# tomu-eagle0.net
KiCad netlist of a schematic drawn in EAGLE
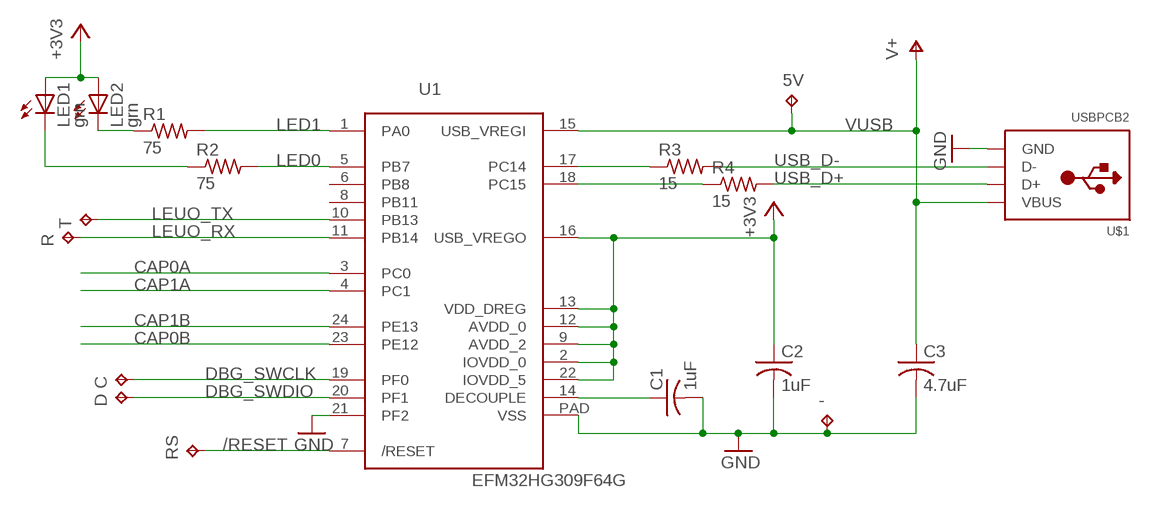
[diagram p0: schematic, sheet 1]

(export (version "E")
  (design (tool "Eeschema 10.0.6"))
  (components
    (comp (ref "-")
      (value "TPTP10SQ")
      (footprint "eagle-import:TP10SQ")
      (libsource (lib "eagle-import") (part "TPTP10SQ"))
    )
    (comp (ref "5V")
      (value "TPTP10R")
      (footprint "eagle-import:TP10R")
      (libsource (lib "eagle-import") (part "TPTP10R"))
    )
    (comp (ref "C")
      (value "TPTP10R")
      (footprint "eagle-import:TP10R")
      (libsource (lib "eagle-import") (part "TPTP10R"))
    )
    (comp (ref "C1")
      (value "1uF")
      (footprint "eagle-import:C0402K")
      (libsource (lib "eagle-import") (part "C-USC0402K"))
    )
    (comp (ref "C2")
      (value "1uF")
      (footprint "eagle-import:C0402K")
      (libsource (lib "eagle-import") (part "C-USC0402K"))
    )
    (comp (ref "C3")
      (value "4.7uF")
      (footprint "eagle-import:C0402K")
      (libsource (lib "eagle-import") (part "C-USC0402K"))
    )
    (comp (ref "D")
      (value "TPTP10R")
      (footprint "eagle-import:TP10R")
      (libsource (lib "eagle-import") (part "TPTP10R"))
    )
    (comp (ref "LED1")
      (value "grn")
      (footprint "eagle-import:CHIP-LED0603")
      (libsource (lib "eagle-import") (part "LEDCHIP-LED0603"))
    )
    (comp (ref "LED2")
      (value "grn")
      (footprint "eagle-import:CHIP-LED0603")
      (libsource (lib "eagle-import") (part "LEDCHIP-LED0603"))
    )
    (comp (ref "R")
      (value "TPTP10R")
      (footprint "eagle-import:TP10R")
      (libsource (lib "eagle-import") (part "TPTP10R"))
    )
    (comp (ref "R1")
      (value "75")
      (footprint "eagle-import:R0402")
      (libsource (lib "eagle-import") (part "R-US_R0402"))
    )
    (comp (ref "R2")
      (value "75")
      (footprint "eagle-import:R0402")
      (libsource (lib "eagle-import") (part "R-US_R0402"))
    )
    (comp (ref "R3")
      (value "15")
      (footprint "eagle-import:R0402")
      (libsource (lib "eagle-import") (part "R-US_R0402"))
    )
    (comp (ref "R4")
      (value "15")
      (footprint "eagle-import:R0402")
      (libsource (lib "eagle-import") (part "R-US_R0402"))
    )
    (comp (ref "RS")
      (value "TPTP10R")
      (footprint "eagle-import:TP10R")
      (libsource (lib "eagle-import") (part "TPTP10R"))
    )
    (comp (ref "T")
      (value "TPTP10R")
      (footprint "eagle-import:TP10R")
      (libsource (lib "eagle-import") (part "TPTP10R"))
    )
    (comp (ref "U$1")
      (value "USBPCB2")
      (footprint "eagle-import:USB-A-PCB-2")
      (libsource (lib "eagle-import") (part "USBPCB2"))
    )
    (comp (ref "U1")
      (value "EFM32HG309F64G")
      (footprint "eagle-import:QFN24PAD")
      (libsource (lib "eagle-import") (part "EFM32HG309F64G"))
    )
  )
  (nets
    (net (code "1") (name "+3V3") (class "Default")
      (node (ref "C2") (pin "1") (pinfunction "1_1") (pintype "passive"))
      (node (ref "LED1") (pin "A") (pinfunction "A_A") (pintype "passive"))
      (node (ref "LED2") (pin "A") (pinfunction "A_A") (pintype "passive"))
      (node (ref "U1") (pin "12") (pinfunction "AVDD_0_12") (pintype "bidirectional"))
      (node (ref "U1") (pin "13") (pinfunction "VDD_DREG_13") (pintype "bidirectional"))
      (node (ref "U1") (pin "16") (pinfunction "USB_VREGO_16") (pintype "bidirectional"))
      (node (ref "U1") (pin "2") (pinfunction "IOVDD_0_2") (pintype "bidirectional"))
      (node (ref "U1") (pin "22") (pinfunction "IOVDD_5_22") (pintype "bidirectional"))
      (node (ref "U1") (pin "9") (pinfunction "AVDD_2_9") (pintype "bidirectional"))
    )
    (net (code "2") (name "/CAP0A") (class "Default")
      (node (ref "U1") (pin "3") (pinfunction "PC0_3") (pintype "bidirectional"))
    )
    (net (code "3") (name "/CAP0B") (class "Default")
      (node (ref "U1") (pin "23") (pinfunction "PE12_23") (pintype "bidirectional"))
    )
    (net (code "4") (name "/CAP1A") (class "Default")
      (node (ref "U1") (pin "4") (pinfunction "PC1_4") (pintype "bidirectional"))
    )
    (net (code "5") (name "/CAP1B") (class "Default")
      (node (ref "U1") (pin "24") (pinfunction "PE13_24") (pintype "bidirectional"))
    )
    (net (code "6") (name "/DBG_SWCLK") (class "Default")
      (node (ref "C") (pin "TP") (pinfunction "TP_TP") (pintype "input"))
      (node (ref "U1") (pin "19") (pinfunction "PF0_19") (pintype "bidirectional"))
    )
    (net (code "7") (name "/DBG_SWDIO") (class "Default")
      (node (ref "D") (pin "TP") (pinfunction "TP_TP") (pintype "input"))
      (node (ref "U1") (pin "20") (pinfunction "PF1_20") (pintype "bidirectional"))
    )
    (net (code "8") (name "/LED0") (class "Default")
      (node (ref "R2") (pin "2") (pinfunction "2_2") (pintype "passive"))
      (node (ref "U1") (pin "5") (pinfunction "PB7_5") (pintype "bidirectional"))
    )
    (net (code "9") (name "/LED1") (class "Default")
      (node (ref "R1") (pin "2") (pinfunction "2_2") (pintype "passive"))
      (node (ref "U1") (pin "1") (pinfunction "PA0_1") (pintype "bidirectional"))
    )
    (net (code "10") (name "/LEUO_RX") (class "Default")
      (node (ref "R") (pin "TP") (pinfunction "TP_TP") (pintype "input"))
      (node (ref "U1") (pin "11") (pinfunction "PB14_11") (pintype "bidirectional"))
    )
    (net (code "11") (name "/LEUO_TX") (class "Default")
      (node (ref "T") (pin "TP") (pinfunction "TP_TP") (pintype "input"))
      (node (ref "U1") (pin "10") (pinfunction "PB13_10") (pintype "bidirectional"))
    )
    (net (code "12") (name "/USB_D+") (class "Default")
      (node (ref "R4") (pin "2") (pinfunction "2_2") (pintype "passive"))
      (node (ref "U$1") (pin "USB_P") (pinfunction "D+_USB_P") (pintype "bidirectional"))
    )
    (net (code "13") (name "/USB_D-") (class "Default")
      (node (ref "R3") (pin "2") (pinfunction "2_2") (pintype "passive"))
      (node (ref "U$1") (pin "USB_M") (pinfunction "D-_USB_M") (pintype "bidirectional"))
    )
    (net (code "14") (name "/{slash}RESET") (class "Default")
      (node (ref "RS") (pin "TP") (pinfunction "TP_TP") (pintype "input"))
      (node (ref "U1") (pin "7") (pinfunction "/RESET_7") (pintype "bidirectional"))
    )
    (net (code "15") (name "GND") (class "Default")
      (node (ref "-") (pin "TP") (pinfunction "TP_TP") (pintype "input"))
      (node (ref "C1") (pin "2") (pinfunction "2_2") (pintype "passive"))
      (node (ref "C2") (pin "2") (pinfunction "2_2") (pintype "passive"))
      (node (ref "C3") (pin "2") (pinfunction "2_2") (pintype "passive"))
      (node (ref "U$1") (pin "GND") (pinfunction "GND_GND") (pintype "power_in"))
      (node (ref "U1") (pin "21") (pinfunction "PF2_21") (pintype "bidirectional"))
      (node (ref "U1") (pin "PAD") (pinfunction "VSS_PAD") (pintype "bidirectional"))
    )
    (net (code "16") (name "Net-(LED1-PadC)") (class "Default")
      (node (ref "LED1") (pin "C") (pinfunction "C_C") (pintype "passive"))
      (node (ref "R2") (pin "1") (pinfunction "1_1") (pintype "passive"))
    )
    (net (code "17") (name "Net-(LED2-PadC)") (class "Default")
      (node (ref "LED2") (pin "C") (pinfunction "C_C") (pintype "passive"))
      (node (ref "R1") (pin "1") (pinfunction "1_1") (pintype "passive"))
    )
    (net (code "18") (name "Net-(U1-DECOUPLE)") (class "Default")
      (node (ref "C1") (pin "1") (pinfunction "1_1") (pintype "passive"))
      (node (ref "U1") (pin "14") (pinfunction "DECOUPLE_14") (pintype "bidirectional"))
    )
    (net (code "19") (name "Net-(U1-PC14)") (class "Default")
      (node (ref "R3") (pin "1") (pinfunction "1_1") (pintype "passive"))
      (node (ref "U1") (pin "17") (pinfunction "PC14_17") (pintype "bidirectional"))
    )
    (net (code "20") (name "Net-(U1-PC15)") (class "Default")
      (node (ref "R4") (pin "1") (pinfunction "1_1") (pintype "passive"))
      (node (ref "U1") (pin "18") (pinfunction "PC15_18") (pintype "bidirectional"))
    )
    (net (code "21") (name "V+") (class "Default")
      (node (ref "5V") (pin "TP") (pinfunction "TP_TP") (pintype "input"))
      (node (ref "C3") (pin "1") (pinfunction "1_1") (pintype "passive"))
      (node (ref "U$1") (pin "5V") (pinfunction "VBUS_5V") (pintype "power_in"))
      (node (ref "U1") (pin "15") (pinfunction "USB_VREGI_15") (pintype "bidirectional"))
    )
    (net (code "22") (name "unconnected-(U1-PB8-Pad6)") (class "Default")
      (node (ref "U1") (pin "6") (pinfunction "PB8_6") (pintype "bidirectional"))
    )
    (net (code "23") (name "unconnected-(U1-PB11-Pad8)") (class "Default")
      (node (ref "U1") (pin "8") (pinfunction "PB11_8") (pintype "bidirectional"))
    )
  )
)
